# rpc_s2_pcb.net
KiCad netlist of a schematic drawn in EasyEDA
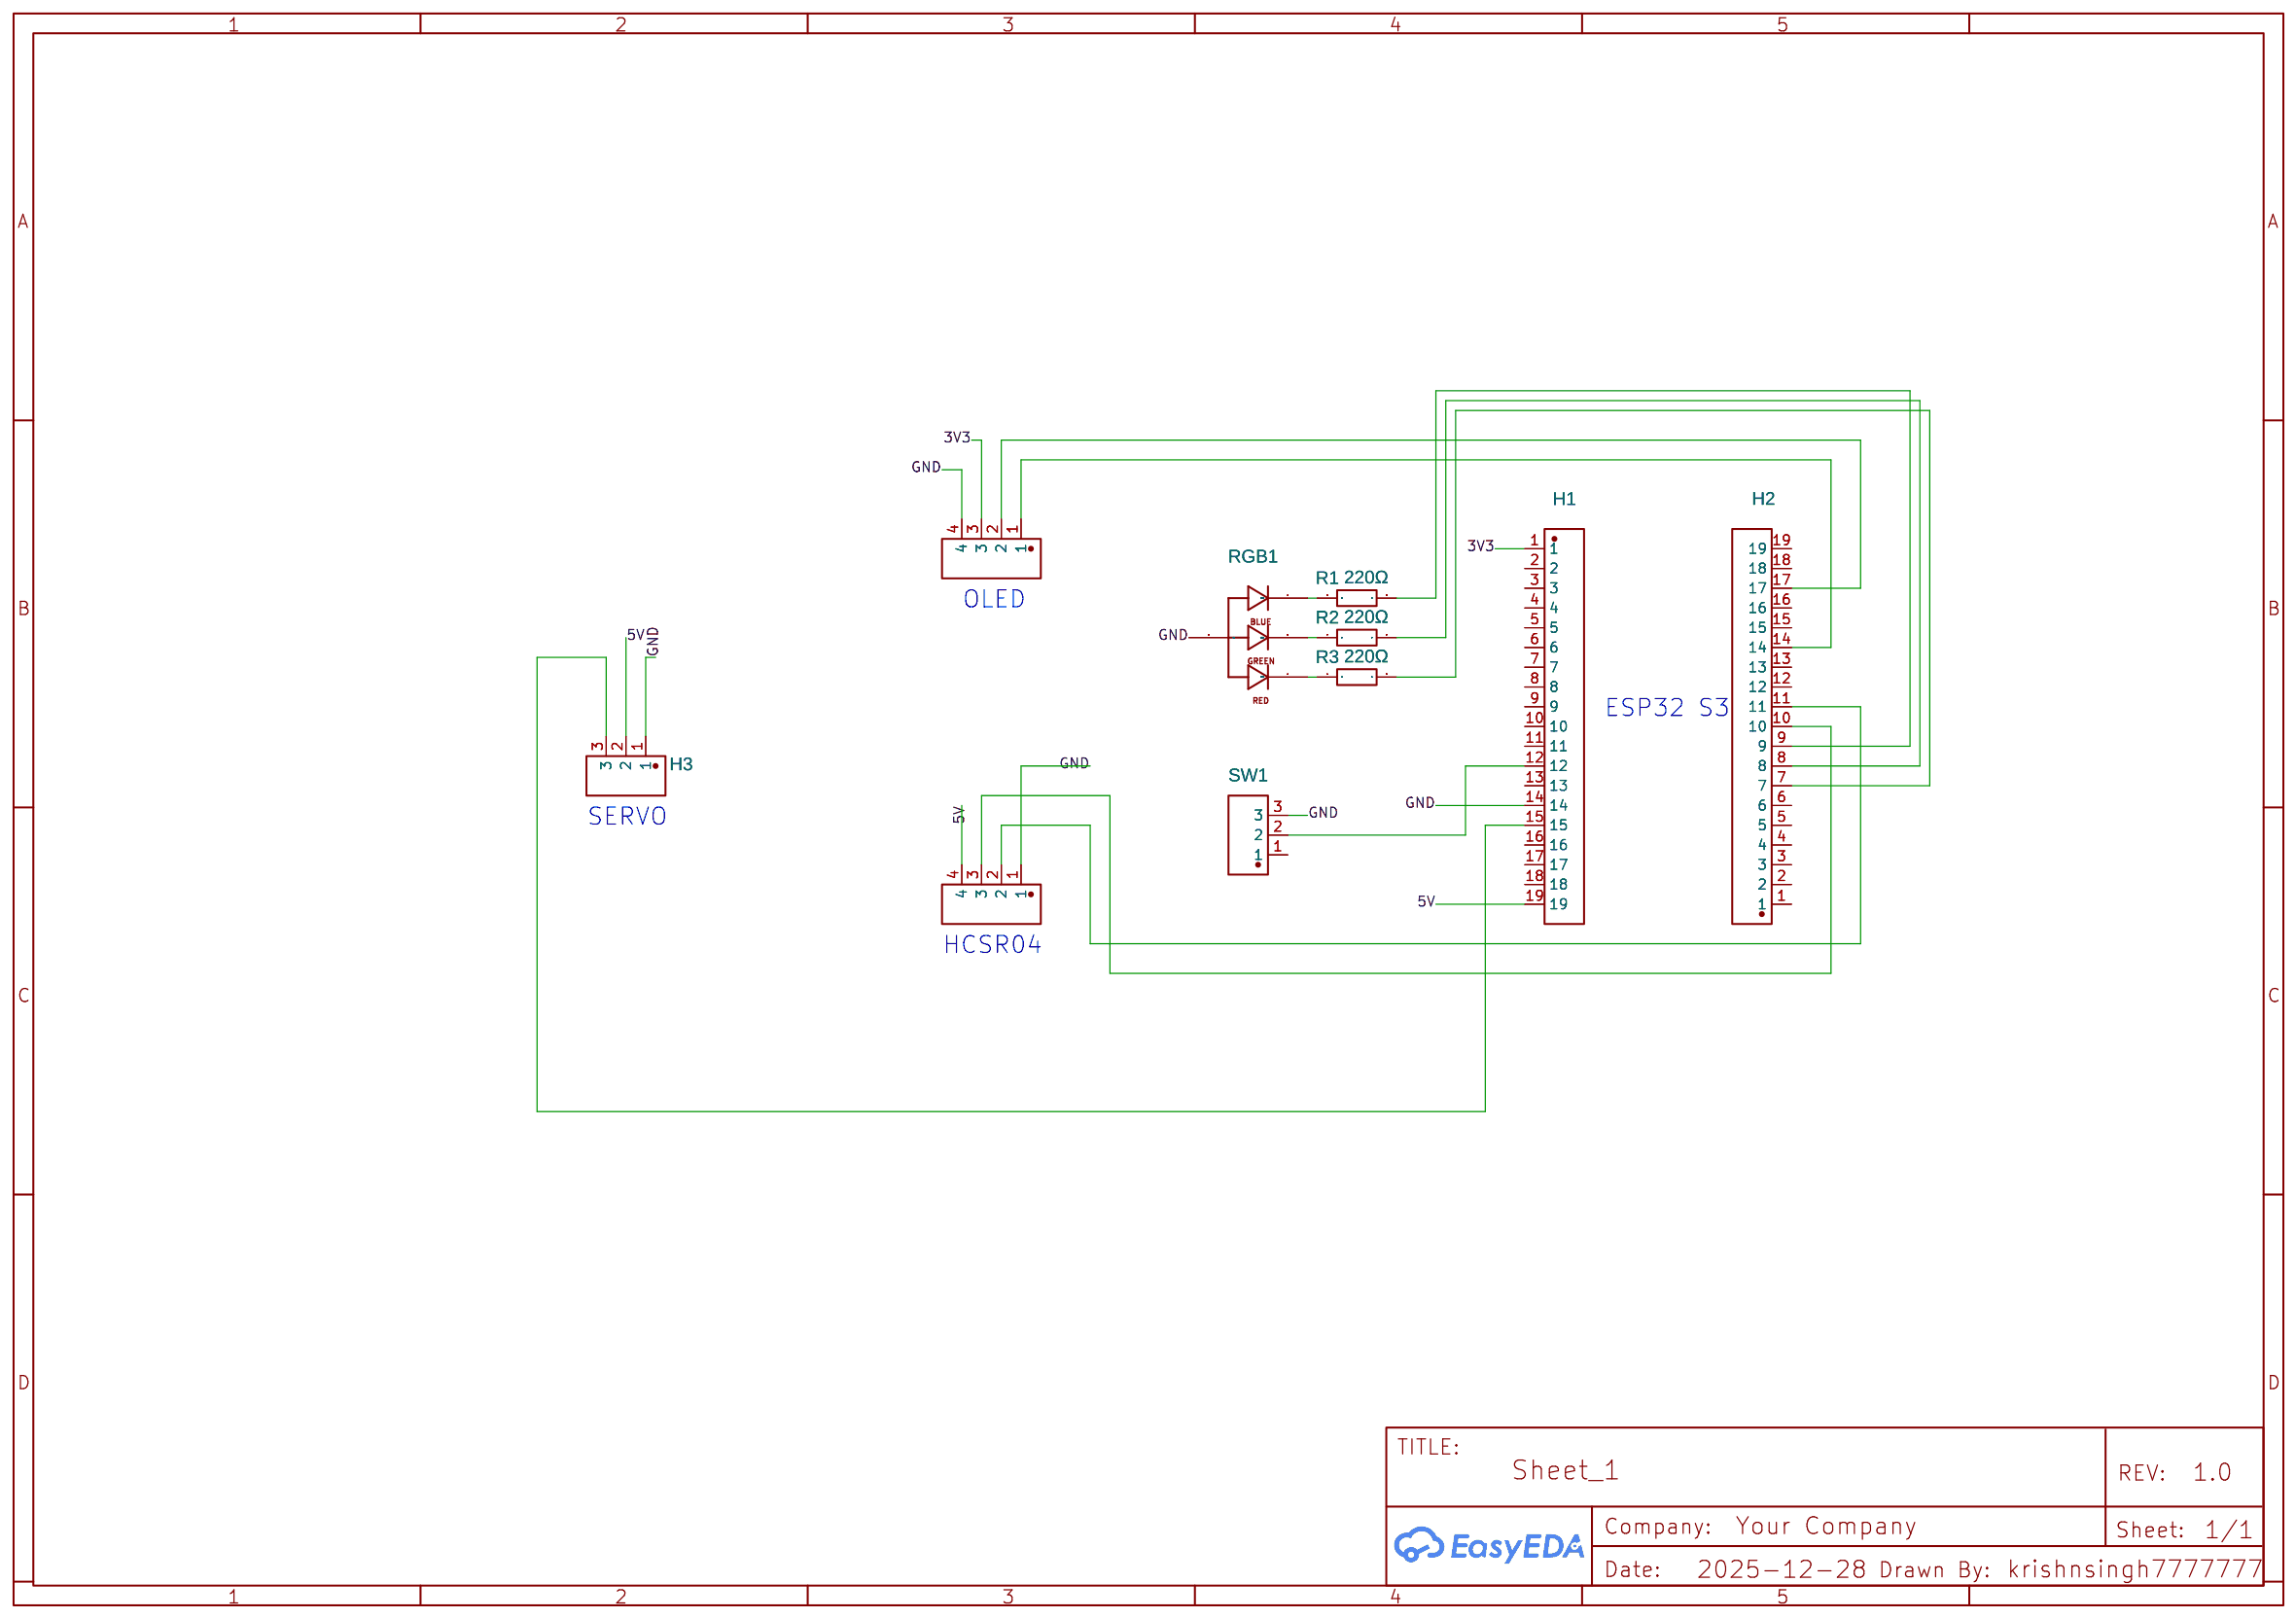
[diagram p0: schematic sheet]

(export (version "E")
  (design (tool "Eeschema 10.0.6"))
  (components
    (comp (ref "CN1")
      (value "OLED")
      (fields (field (name "Manufacturer Part") "Straight 4 pins magnetic connector Female"))
      (libsource (lib "") (part "STRAIGHT 4 PINS MAGNETIC CONNECTOR FEMALE"))
    )
    (comp (ref "CN2")
      (value "HCSR04")
      (fields (field (name "Manufacturer Part") "Straight 4 pins magnetic connector Female"))
      (libsource (lib "") (part "STRAIGHT 4 PINS MAGNETIC CONNECTOR FEMALE"))
    )
    (comp (ref "H1")
      (value "KH-2.54PH180-1X19P-L11.5")
      (fields (field (name "Manufacturer") "kinghelm(金航标)"))
      (libsource (lib "") (part "KH-2.54PH180-1X19P-L11.5_1"))
    )
    (comp (ref "H2")
      (value "KH-2.54PH180-1X19P-L11.5")
      (fields (field (name "Manufacturer") "kinghelm(金航标)"))
      (libsource (lib "") (part "KH-2.54PH180-1X19P-L11.5"))
    )
    (comp (ref "H3")
      (value "SRVO")
      (fields
        (field (name "Manufacturer Part") "HX PH254-01-03-Z-L11.5 pcb pin header")
        (field (name "Manufacturer") "hanxia(韩下)")
      )
      (libsource (lib "") (part "HX PH254-01-03-Z-L11.5 PCB PIN HEADER"))
    )
    (comp (ref "R1")
      (value "220Ω")
      (fields (field (name "Manufacturer Part") "AC0603FR-07220RL") (field (name "Manufacturer") "YAGEO(国巨)"))
      (libsource (lib "") (part "AC0603FR-07220RL"))
    )
    (comp (ref "R2")
      (value "220Ω")
      (fields (field (name "Manufacturer Part") "AC0603FR-07220RL") (field (name "Manufacturer") "YAGEO(国巨)"))
      (libsource (lib "") (part "AC0603FR-07220RL"))
    )
    (comp (ref "R3")
      (value "220Ω")
      (fields (field (name "Manufacturer Part") "AC0603FR-07220RL") (field (name "Manufacturer") "YAGEO(国巨)"))
      (libsource (lib "") (part "AC0603FR-07220RL"))
    )
    (comp (ref "RGB1") (value "RGB") (libsource (lib "") (part "LED-RGB-CA-THRUDIFFUSE")))
    (comp (ref "SW1")
      (value "SW1")
      (fields
        (field (name "Manufacturer Part") "SS-12D10L10")
        (field (name "Manufacturer") "XKB Connection(中国星坤)")
      )
      (libsource (lib "") (part "SS-12D10L10"))
    )
  )
  (nets
    (net (code "1") (name "/3V3") (class "Default")
      (node (ref "CN1") (pin "3") (pinfunction "3_3") (pintype "unspecified"))
      (node (ref "H1") (pin "1") (pinfunction "1_1") (pintype "unspecified"))
    )
    (net (code "2") (name "/5V") (class "Default")
      (node (ref "CN2") (pin "4") (pinfunction "4_4") (pintype "unspecified"))
      (node (ref "H1") (pin "19") (pinfunction "19_19") (pintype "unspecified"))
      (node (ref "H3") (pin "2") (pinfunction "2_2") (pintype "unspecified"))
    )
    (net (code "3") (name "/GND") (class "Default")
      (node (ref "CN1") (pin "4") (pinfunction "4_4") (pintype "unspecified"))
      (node (ref "CN2") (pin "1") (pinfunction "1_1") (pintype "unspecified"))
      (node (ref "H1") (pin "14") (pinfunction "14_14") (pintype "unspecified"))
      (node (ref "H3") (pin "1") (pinfunction "1_1") (pintype "unspecified"))
      (node (ref "RGB1") (pin "2") (pinfunction "ANODE_2") (pintype "unspecified"))
      (node (ref "SW1") (pin "3") (pinfunction "3_3") (pintype "unspecified"))
    )
    (net (code "4") (name "Net-(CN1-Pad1)") (class "Default")
      (node (ref "CN1") (pin "1") (pinfunction "1_1") (pintype "unspecified"))
      (node (ref "H2") (pin "14") (pinfunction "14_14") (pintype "unspecified"))
    )
    (net (code "5") (name "Net-(CN1-Pad2)") (class "Default")
      (node (ref "CN1") (pin "2") (pinfunction "2_2") (pintype "unspecified"))
      (node (ref "H2") (pin "17") (pinfunction "17_17") (pintype "unspecified"))
    )
    (net (code "6") (name "Net-(CN2-Pad2)") (class "Default")
      (node (ref "CN2") (pin "2") (pinfunction "2_2") (pintype "unspecified"))
      (node (ref "H2") (pin "11") (pinfunction "11_11") (pintype "unspecified"))
    )
    (net (code "7") (name "Net-(CN2-Pad3)") (class "Default")
      (node (ref "CN2") (pin "3") (pinfunction "3_3") (pintype "unspecified"))
      (node (ref "H2") (pin "10") (pinfunction "10_10") (pintype "unspecified"))
    )
    (net (code "8") (name "Net-(H1-Pad12)") (class "Default")
      (node (ref "H1") (pin "12") (pinfunction "12_12") (pintype "unspecified"))
      (node (ref "SW1") (pin "2") (pinfunction "2_2") (pintype "unspecified"))
    )
    (net (code "9") (name "Net-(H1-Pad15)") (class "Default")
      (node (ref "H1") (pin "15") (pinfunction "15_15") (pintype "unspecified"))
      (node (ref "H3") (pin "3") (pinfunction "3_3") (pintype "unspecified"))
    )
    (net (code "10") (name "Net-(H2-Pad7)") (class "Default")
      (node (ref "H2") (pin "7") (pinfunction "7_7") (pintype "unspecified"))
      (node (ref "R3") (pin "2") (pinfunction "2_2") (pintype "input"))
    )
    (net (code "11") (name "Net-(H2-Pad8)") (class "Default")
      (node (ref "H2") (pin "8") (pinfunction "8_8") (pintype "unspecified"))
      (node (ref "R2") (pin "2") (pinfunction "2_2") (pintype "input"))
    )
    (net (code "12") (name "Net-(H2-Pad9)") (class "Default")
      (node (ref "H2") (pin "9") (pinfunction "9_9") (pintype "unspecified"))
      (node (ref "R1") (pin "2") (pinfunction "2_2") (pintype "input"))
    )
    (net (code "13") (name "Net-(RGB1-BLUE_CATHODE)") (class "Default")
      (node (ref "R1") (pin "1") (pinfunction "1_1") (pintype "input"))
      (node (ref "RGB1") (pin "4") (pinfunction "BLUE_CATHODE_4") (pintype "unspecified"))
    )
    (net (code "14") (name "Net-(RGB1-GREEN_CATHODE)") (class "Default")
      (node (ref "R2") (pin "1") (pinfunction "1_1") (pintype "input"))
      (node (ref "RGB1") (pin "3") (pinfunction "GREEN_CATHODE_3") (pintype "unspecified"))
    )
    (net (code "15") (name "Net-(RGB1-RED_CATHODE)") (class "Default")
      (node (ref "R3") (pin "1") (pinfunction "1_1") (pintype "input"))
      (node (ref "RGB1") (pin "1") (pinfunction "RED_CATHODE_1") (pintype "unspecified"))
    )
    (net (code "16") (name "unconnected-(H1-Pad2)") (class "Default")
      (node (ref "H1") (pin "2") (pinfunction "2_2") (pintype "unspecified"))
    )
    (net (code "17") (name "unconnected-(H1-Pad3)") (class "Default")
      (node (ref "H1") (pin "3") (pinfunction "3_3") (pintype "unspecified"))
    )
    (net (code "18") (name "unconnected-(H1-Pad4)") (class "Default")
      (node (ref "H1") (pin "4") (pinfunction "4_4") (pintype "unspecified"))
    )
    (net (code "19") (name "unconnected-(H1-Pad5)") (class "Default")
      (node (ref "H1") (pin "5") (pinfunction "5_5") (pintype "unspecified"))
    )
    (net (code "20") (name "unconnected-(H1-Pad6)") (class "Default")
      (node (ref "H1") (pin "6") (pinfunction "6_6") (pintype "unspecified"))
    )
    (net (code "21") (name "unconnected-(H1-Pad7)") (class "Default")
      (node (ref "H1") (pin "7") (pinfunction "7_7") (pintype "unspecified"))
    )
    (net (code "22") (name "unconnected-(H1-Pad8)") (class "Default")
      (node (ref "H1") (pin "8") (pinfunction "8_8") (pintype "unspecified"))
    )
    (net (code "23") (name "unconnected-(H1-Pad9)") (class "Default")
      (node (ref "H1") (pin "9") (pinfunction "9_9") (pintype "unspecified"))
    )
    (net (code "24") (name "unconnected-(H1-Pad10)") (class "Default")
      (node (ref "H1") (pin "10") (pinfunction "10_10") (pintype "unspecified"))
    )
    (net (code "25") (name "unconnected-(H1-Pad11)") (class "Default")
      (node (ref "H1") (pin "11") (pinfunction "11_11") (pintype "unspecified"))
    )
    (net (code "26") (name "unconnected-(H1-Pad13)") (class "Default")
      (node (ref "H1") (pin "13") (pinfunction "13_13") (pintype "unspecified"))
    )
    (net (code "27") (name "unconnected-(H1-Pad16)") (class "Default")
      (node (ref "H1") (pin "16") (pinfunction "16_16") (pintype "unspecified"))
    )
    (net (code "28") (name "unconnected-(H1-Pad17)") (class "Default")
      (node (ref "H1") (pin "17") (pinfunction "17_17") (pintype "unspecified"))
    )
    (net (code "29") (name "unconnected-(H1-Pad18)") (class "Default")
      (node (ref "H1") (pin "18") (pinfunction "18_18") (pintype "unspecified"))
    )
    (net (code "30") (name "unconnected-(H2-Pad1)") (class "Default")
      (node (ref "H2") (pin "1") (pinfunction "1_1") (pintype "unspecified"))
    )
    (net (code "31") (name "unconnected-(H2-Pad2)") (class "Default")
      (node (ref "H2") (pin "2") (pinfunction "2_2") (pintype "unspecified"))
    )
    (net (code "32") (name "unconnected-(H2-Pad3)") (class "Default")
      (node (ref "H2") (pin "3") (pinfunction "3_3") (pintype "unspecified"))
    )
    (net (code "33") (name "unconnected-(H2-Pad4)") (class "Default")
      (node (ref "H2") (pin "4") (pinfunction "4_4") (pintype "unspecified"))
    )
    (net (code "34") (name "unconnected-(H2-Pad5)") (class "Default")
      (node (ref "H2") (pin "5") (pinfunction "5_5") (pintype "unspecified"))
    )
    (net (code "35") (name "unconnected-(H2-Pad6)") (class "Default")
      (node (ref "H2") (pin "6") (pinfunction "6_6") (pintype "unspecified"))
    )
    (net (code "36") (name "unconnected-(H2-Pad12)") (class "Default")
      (node (ref "H2") (pin "12") (pinfunction "12_12") (pintype "unspecified"))
    )
    (net (code "37") (name "unconnected-(H2-Pad13)") (class "Default")
      (node (ref "H2") (pin "13") (pinfunction "13_13") (pintype "unspecified"))
    )
    (net (code "38") (name "unconnected-(H2-Pad15)") (class "Default")
      (node (ref "H2") (pin "15") (pinfunction "15_15") (pintype "unspecified"))
    )
    (net (code "39") (name "unconnected-(H2-Pad16)") (class "Default")
      (node (ref "H2") (pin "16") (pinfunction "16_16") (pintype "unspecified"))
    )
    (net (code "40") (name "unconnected-(H2-Pad18)") (class "Default")
      (node (ref "H2") (pin "18") (pinfunction "18_18") (pintype "unspecified"))
    )
    (net (code "41") (name "unconnected-(H2-Pad19)") (class "Default")
      (node (ref "H2") (pin "19") (pinfunction "19_19") (pintype "unspecified"))
    )
    (net (code "42") (name "unconnected-(SW1-Pad1)") (class "Default")
      (node (ref "SW1") (pin "1") (pinfunction "1_1") (pintype "unspecified"))
    )
  )
)
